# Tx.net
KiCad netlist of a schematic drawn in EAGLE
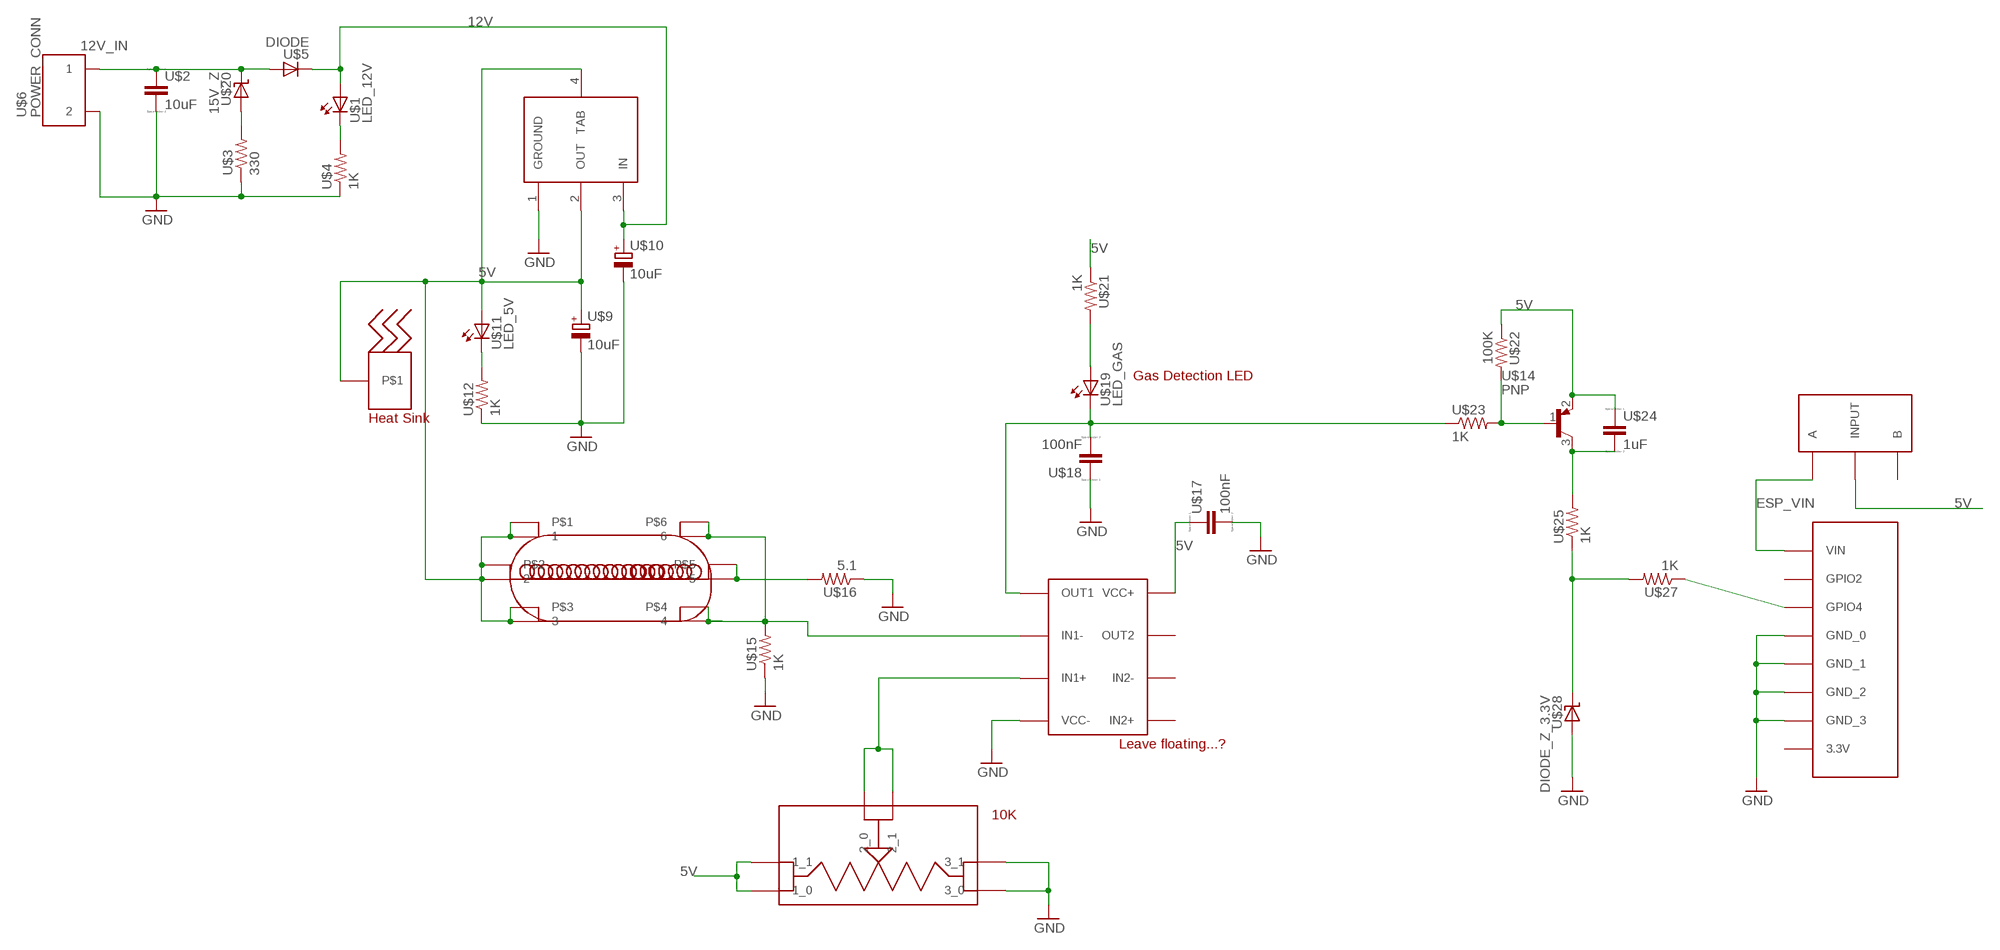
[diagram p0: schematic, sheet 1]

(export (version "E")
  (design (tool "Eeschema 10.0.6"))
  (components
    (comp (ref "U$1")
      (value "LED_12V")
      (footprint "eagle-import:LED_1206")
      (libsource (lib "eagle-import") (part "LED_1206"))
    )
    (comp (ref "U$2")
      (value "10uF")
      (footprint "eagle-import:C1206")
      (libsource (lib "eagle-import") (part "CAP"))
    )
    (comp (ref "U$3")
      (value "330")
      (footprint "eagle-import:R1206")
      (libsource (lib "eagle-import") (part "RES"))
    )
    (comp (ref "U$4")
      (value "1K")
      (footprint "eagle-import:R1206")
      (libsource (lib "eagle-import") (part "RES"))
    )
    (comp (ref "U$5")
      (value "DIODE")
      (footprint "eagle-import:DIDOE_1206")
      (libsource (lib "eagle-import") (part "DIODE_1206"))
    )
    (comp (ref "U$6")
      (value "POWER_CONN")
      (footprint "eagle-import:PC_1935161")
      (libsource (lib "eagle-import") (part "POWER_CONN"))
    )
    (comp (ref "U$7")
      (value "LM393")
      (footprint "eagle-import:SO8")
      (libsource (lib "eagle-import") (part "LM393"))
    )
    (comp (ref "U$8")
      (value "5V_REG")
      (footprint "eagle-import:SOT223")
      (libsource (lib "eagle-import") (part "5V_REG"))
    )
    (comp (ref "U$9")
      (value "10uF")
      (footprint "eagle-import:153CLV-0405")
      (libsource (lib "eagle-import") (part "CAP_POL"))
    )
    (comp (ref "U$10")
      (value "10uF")
      (footprint "eagle-import:153CLV-0405")
      (libsource (lib "eagle-import") (part "CAP_POL"))
    )
    (comp (ref "U$11")
      (value "LED_5V")
      (footprint "eagle-import:LED_1206")
      (libsource (lib "eagle-import") (part "LED_1206"))
    )
    (comp (ref "U$12")
      (value "1K")
      (footprint "eagle-import:R1206")
      (libsource (lib "eagle-import") (part "RES"))
    )
    (comp (ref "U$13")
      (value "MQ")
      (footprint "eagle-import:MQ_GAS")
      (libsource (lib "eagle-import") (part "MQ"))
    )
    (comp (ref "U$14")
      (value "PNP")
      (footprint "eagle-import:SOT23")
      (libsource (lib "eagle-import") (part "PNP"))
    )
    (comp (ref "U$15")
      (value "1K")
      (footprint "eagle-import:R1206")
      (libsource (lib "eagle-import") (part "RES"))
    )
    (comp (ref "U$16")
      (value "5.1")
      (footprint "eagle-import:R1206")
      (libsource (lib "eagle-import") (part "RES"))
    )
    (comp (ref "U$17")
      (value "100nF")
      (footprint "eagle-import:C1206")
      (libsource (lib "eagle-import") (part "CAP"))
    )
    (comp (ref "U$18")
      (value "100nF")
      (footprint "eagle-import:C1206")
      (libsource (lib "eagle-import") (part "CAP"))
    )
    (comp (ref "U$19")
      (value "LED_GAS")
      (footprint "eagle-import:LED_1206")
      (libsource (lib "eagle-import") (part "LED_1206"))
    )
    (comp (ref "U$20")
      (value "15V_Z")
      (footprint "eagle-import:Z_1005")
      (libsource (lib "eagle-import") (part "DIODE_Z_1005"))
    )
    (comp (ref "U$21")
      (value "1K")
      (footprint "eagle-import:R1206")
      (libsource (lib "eagle-import") (part "RES"))
    )
    (comp (ref "U$22")
      (value "100K")
      (footprint "eagle-import:R1206")
      (libsource (lib "eagle-import") (part "RES"))
    )
    (comp (ref "U$23")
      (value "1K")
      (footprint "eagle-import:R1206")
      (libsource (lib "eagle-import") (part "RES"))
    )
    (comp (ref "U$24")
      (value "1uF")
      (footprint "eagle-import:C1206")
      (libsource (lib "eagle-import") (part "CAP"))
    )
    (comp (ref "U$25")
      (value "1K")
      (footprint "eagle-import:R1206")
      (libsource (lib "eagle-import") (part "RES"))
    )
    (comp (ref "U$27")
      (value "1K")
      (footprint "eagle-import:R1206")
      (libsource (lib "eagle-import") (part "RES"))
    )
    (comp (ref "U$28")
      (value "DIODE_Z_3.3V")
      (footprint "eagle-import:SOD-323")
      (libsource (lib "eagle-import") (part "DIODE_Z_3.3V"))
    )
    (comp (ref "U$29")
      (value "ESP8266")
      (footprint "eagle-import:ESP")
      (libsource (lib "eagle-import") (part "ESP8266"))
    )
    (comp (ref "U$30")
      (value "POTENTIOMETER")
      (footprint "eagle-import:POTENTIOMETER")
      (libsource (lib "eagle-import") (part "POTENTIOMETER"))
    )
    (comp (ref "U$31")
      (value "HEAT_SINK")
      (footprint "eagle-import:THERMAL")
      (libsource (lib "eagle-import") (part "HEAT_SINK"))
    )
    (comp (ref "U$32")
      (value "SPDT")
      (footprint "eagle-import:SPDT")
      (libsource (lib "eagle-import") (part "SPDT"))
    )
  )
  (nets
    (net (code "1") (name "/5V") (class "Default")
      (node (ref "U$11") (pin "1") (pinfunction "HI_1") (pintype "bidirectional"))
      (node (ref "U$13") (pin "1") (pinfunction "1_1") (pintype "bidirectional"))
      (node (ref "U$13") (pin "2") (pinfunction "2_2") (pintype "bidirectional"))
      (node (ref "U$13") (pin "3") (pinfunction "3_3") (pintype "bidirectional"))
      (node (ref "U$13") (pin "7") (pinfunction "P$1_7") (pintype "bidirectional"))
      (node (ref "U$13") (pin "8") (pinfunction "P$2_8") (pintype "bidirectional"))
      (node (ref "U$13") (pin "9") (pinfunction "P$3_9") (pintype "bidirectional"))
      (node (ref "U$14") (pin "2") (pinfunction "E_2") (pintype "passive"))
      (node (ref "U$17") (pin "1") (pinfunction "1_1") (pintype "passive"))
      (node (ref "U$21") (pin "1") (pinfunction "1_1") (pintype "passive"))
      (node (ref "U$22") (pin "1") (pinfunction "1_1") (pintype "passive"))
      (node (ref "U$24") (pin "1") (pinfunction "1_1") (pintype "passive"))
      (node (ref "U$30") (pin "1_0") (pinfunction "1_0_1_0") (pintype "bidirectional"))
      (node (ref "U$30") (pin "1_1") (pinfunction "1_1_1_1") (pintype "bidirectional"))
      (node (ref "U$31") (pin "P$1") (pinfunction "P$1_P$1") (pintype "bidirectional"))
      (node (ref "U$32") (pin "IN") (pinfunction "INPUT_IN") (pintype "bidirectional"))
      (node (ref "U$7") (pin "8") (pinfunction "VCC+_8") (pintype "bidirectional"))
      (node (ref "U$8") (pin "2") (pinfunction "OUT_2") (pintype "bidirectional"))
      (node (ref "U$8") (pin "4") (pinfunction "TAB_4") (pintype "bidirectional"))
      (node (ref "U$9") (pin "+") (pinfunction "+_+") (pintype "passive"))
    )
    (net (code "2") (name "/12V") (class "Default")
      (node (ref "U$1") (pin "1") (pinfunction "HI_1") (pintype "bidirectional"))
      (node (ref "U$10") (pin "+") (pinfunction "+_+") (pintype "passive"))
      (node (ref "U$5") (pin "2") (pinfunction "LO_2") (pintype "bidirectional"))
      (node (ref "U$8") (pin "3") (pinfunction "IN_3") (pintype "bidirectional"))
    )
    (net (code "3") (name "/12V_IN") (class "Default")
      (node (ref "U$2") (pin "1") (pinfunction "1_1") (pintype "passive"))
      (node (ref "U$20") (pin "2") (pinfunction "LO_2") (pintype "bidirectional"))
      (node (ref "U$5") (pin "1") (pinfunction "HI_1") (pintype "bidirectional"))
      (node (ref "U$6") (pin "1") (pinfunction "1_1") (pintype "passive"))
    )
    (net (code "4") (name "/ESP_VIN") (class "Default")
      (node (ref "U$29") (pin "VIN") (pinfunction "VIN_VIN") (pintype "bidirectional"))
      (node (ref "U$32") (pin "A") (pinfunction "A_A") (pintype "bidirectional"))
    )
    (net (code "5") (name "GND") (class "Default")
      (node (ref "U$10") (pin "-") (pinfunction "-_-") (pintype "passive"))
      (node (ref "U$12") (pin "1") (pinfunction "1_1") (pintype "passive"))
      (node (ref "U$15") (pin "1") (pinfunction "1_1") (pintype "passive"))
      (node (ref "U$16") (pin "1") (pinfunction "1_1") (pintype "passive"))
      (node (ref "U$17") (pin "2") (pinfunction "2_2") (pintype "passive"))
      (node (ref "U$18") (pin "1") (pinfunction "1_1") (pintype "passive"))
      (node (ref "U$2") (pin "2") (pinfunction "2_2") (pintype "passive"))
      (node (ref "U$28") (pin "P$1") (pinfunction "HI_P$1") (pintype "bidirectional"))
      (node (ref "U$29") (pin "GND_0") (pinfunction "GND_0_GND_0") (pintype "bidirectional"))
      (node (ref "U$29") (pin "GND_1") (pinfunction "GND_1_GND_1") (pintype "bidirectional"))
      (node (ref "U$29") (pin "GND_2") (pinfunction "GND_2_GND_2") (pintype "bidirectional"))
      (node (ref "U$29") (pin "GND_3") (pinfunction "GND_3_GND_3") (pintype "bidirectional"))
      (node (ref "U$3") (pin "1") (pinfunction "1_1") (pintype "passive"))
      (node (ref "U$30") (pin "3_0") (pinfunction "3_0_3_0") (pintype "bidirectional"))
      (node (ref "U$30") (pin "3_1") (pinfunction "3_1_3_1") (pintype "bidirectional"))
      (node (ref "U$4") (pin "1") (pinfunction "1_1") (pintype "passive"))
      (node (ref "U$6") (pin "2") (pinfunction "2_2") (pintype "passive"))
      (node (ref "U$7") (pin "4") (pinfunction "VCC-_4") (pintype "bidirectional"))
      (node (ref "U$8") (pin "1") (pinfunction "GROUND_1") (pintype "bidirectional"))
      (node (ref "U$9") (pin "-") (pinfunction "-_-") (pintype "passive"))
    )
    (net (code "6") (name "Net-(U$1-LO)") (class "Default")
      (node (ref "U$1") (pin "2") (pinfunction "LO_2") (pintype "bidirectional"))
      (node (ref "U$4") (pin "2") (pinfunction "2_2") (pintype "passive"))
    )
    (net (code "7") (name "Net-(U$7-IN1+)") (class "Default")
      (node (ref "U$30") (pin "2_0") (pinfunction "2_0_2_0") (pintype "bidirectional"))
      (node (ref "U$30") (pin "2_1") (pinfunction "2_1_2_1") (pintype "bidirectional"))
      (node (ref "U$7") (pin "3") (pinfunction "IN1+_3") (pintype "bidirectional"))
    )
    (net (code "8") (name "Net-(U$11-LO)") (class "Default")
      (node (ref "U$11") (pin "2") (pinfunction "LO_2") (pintype "bidirectional"))
      (node (ref "U$12") (pin "2") (pinfunction "2_2") (pintype "passive"))
    )
    (net (code "9") (name "Net-(U$13-P$4)") (class "Default")
      (node (ref "U$13") (pin "10") (pinfunction "P$4_10") (pintype "bidirectional"))
      (node (ref "U$13") (pin "12") (pinfunction "P$6_12") (pintype "bidirectional"))
      (node (ref "U$13") (pin "4") (pinfunction "4_4") (pintype "bidirectional"))
      (node (ref "U$13") (pin "6") (pinfunction "6_6") (pintype "bidirectional"))
      (node (ref "U$15") (pin "2") (pinfunction "2_2") (pintype "passive"))
      (node (ref "U$7") (pin "2") (pinfunction "IN1-_2") (pintype "bidirectional"))
    )
    (net (code "10") (name "Net-(U$13-P$5)") (class "Default")
      (node (ref "U$13") (pin "11") (pinfunction "P$5_11") (pintype "bidirectional"))
      (node (ref "U$13") (pin "5") (pinfunction "5_5") (pintype "bidirectional"))
      (node (ref "U$16") (pin "2") (pinfunction "2_2") (pintype "passive"))
    )
    (net (code "11") (name "Net-(U$14-B)") (class "Default")
      (node (ref "U$14") (pin "1") (pinfunction "B_1") (pintype "passive"))
      (node (ref "U$22") (pin "2") (pinfunction "2_2") (pintype "passive"))
      (node (ref "U$23") (pin "2") (pinfunction "2_2") (pintype "passive"))
    )
    (net (code "12") (name "Net-(U$14-C)") (class "Default")
      (node (ref "U$14") (pin "3") (pinfunction "C_3") (pintype "passive"))
      (node (ref "U$24") (pin "2") (pinfunction "2_2") (pintype "passive"))
      (node (ref "U$25") (pin "2") (pinfunction "2_2") (pintype "passive"))
    )
    (net (code "13") (name "Net-(U$19-HI)") (class "Default")
      (node (ref "U$19") (pin "1") (pinfunction "HI_1") (pintype "bidirectional"))
      (node (ref "U$21") (pin "2") (pinfunction "2_2") (pintype "passive"))
    )
    (net (code "14") (name "Net-(U$19-LO)") (class "Default")
      (node (ref "U$18") (pin "2") (pinfunction "2_2") (pintype "passive"))
      (node (ref "U$19") (pin "2") (pinfunction "LO_2") (pintype "bidirectional"))
      (node (ref "U$23") (pin "1") (pinfunction "1_1") (pintype "passive"))
      (node (ref "U$7") (pin "1") (pinfunction "OUT1_1") (pintype "bidirectional"))
    )
    (net (code "15") (name "Net-(U$20-HI)") (class "Default")
      (node (ref "U$20") (pin "1") (pinfunction "HI_1") (pintype "bidirectional"))
      (node (ref "U$3") (pin "2") (pinfunction "2_2") (pintype "passive"))
    )
    (net (code "16") (name "Net-(U$27-Pad1)") (class "Default")
      (node (ref "U$27") (pin "1") (pinfunction "1_1") (pintype "passive"))
      (node (ref "U$29") (pin "GPIO4") (pinfunction "GPIO4_GPIO4") (pintype "bidirectional"))
    )
    (net (code "17") (name "Net-(U$28-LO)") (class "Default")
      (node (ref "U$25") (pin "1") (pinfunction "1_1") (pintype "passive"))
      (node (ref "U$27") (pin "2") (pinfunction "2_2") (pintype "passive"))
      (node (ref "U$28") (pin "P$2") (pinfunction "LO_P$2") (pintype "bidirectional"))
    )
    (net (code "18") (name "unconnected-(U$7-IN2+-Pad5)") (class "Default")
      (node (ref "U$7") (pin "5") (pinfunction "IN2+_5") (pintype "bidirectional"))
    )
    (net (code "19") (name "unconnected-(U$7-IN2--Pad6)") (class "Default")
      (node (ref "U$7") (pin "6") (pinfunction "IN2-_6") (pintype "bidirectional"))
    )
    (net (code "20") (name "unconnected-(U$7-OUT2-Pad7)") (class "Default")
      (node (ref "U$7") (pin "7") (pinfunction "OUT2_7") (pintype "bidirectional"))
    )
    (net (code "21") (name "unconnected-(U$29-3.3V-Pad3.3_1)") (class "Default")
      (node (ref "U$29") (pin "3.3_1") (pinfunction "3.3V_3.3_1") (pintype "bidirectional"))
    )
    (net (code "22") (name "unconnected-(U$29-PadGPIO2)") (class "Default")
      (node (ref "U$29") (pin "GPIO2") (pinfunction "GPIO2_GPIO2") (pintype "bidirectional"))
    )
    (net (code "23") (name "unconnected-(U$32-PadB)") (class "Default")
      (node (ref "U$32") (pin "B") (pinfunction "B_B") (pintype "bidirectional"))
    )
  )
)
